# lotokey.net
KiCad netlist of a schematic drawn in EAGLE
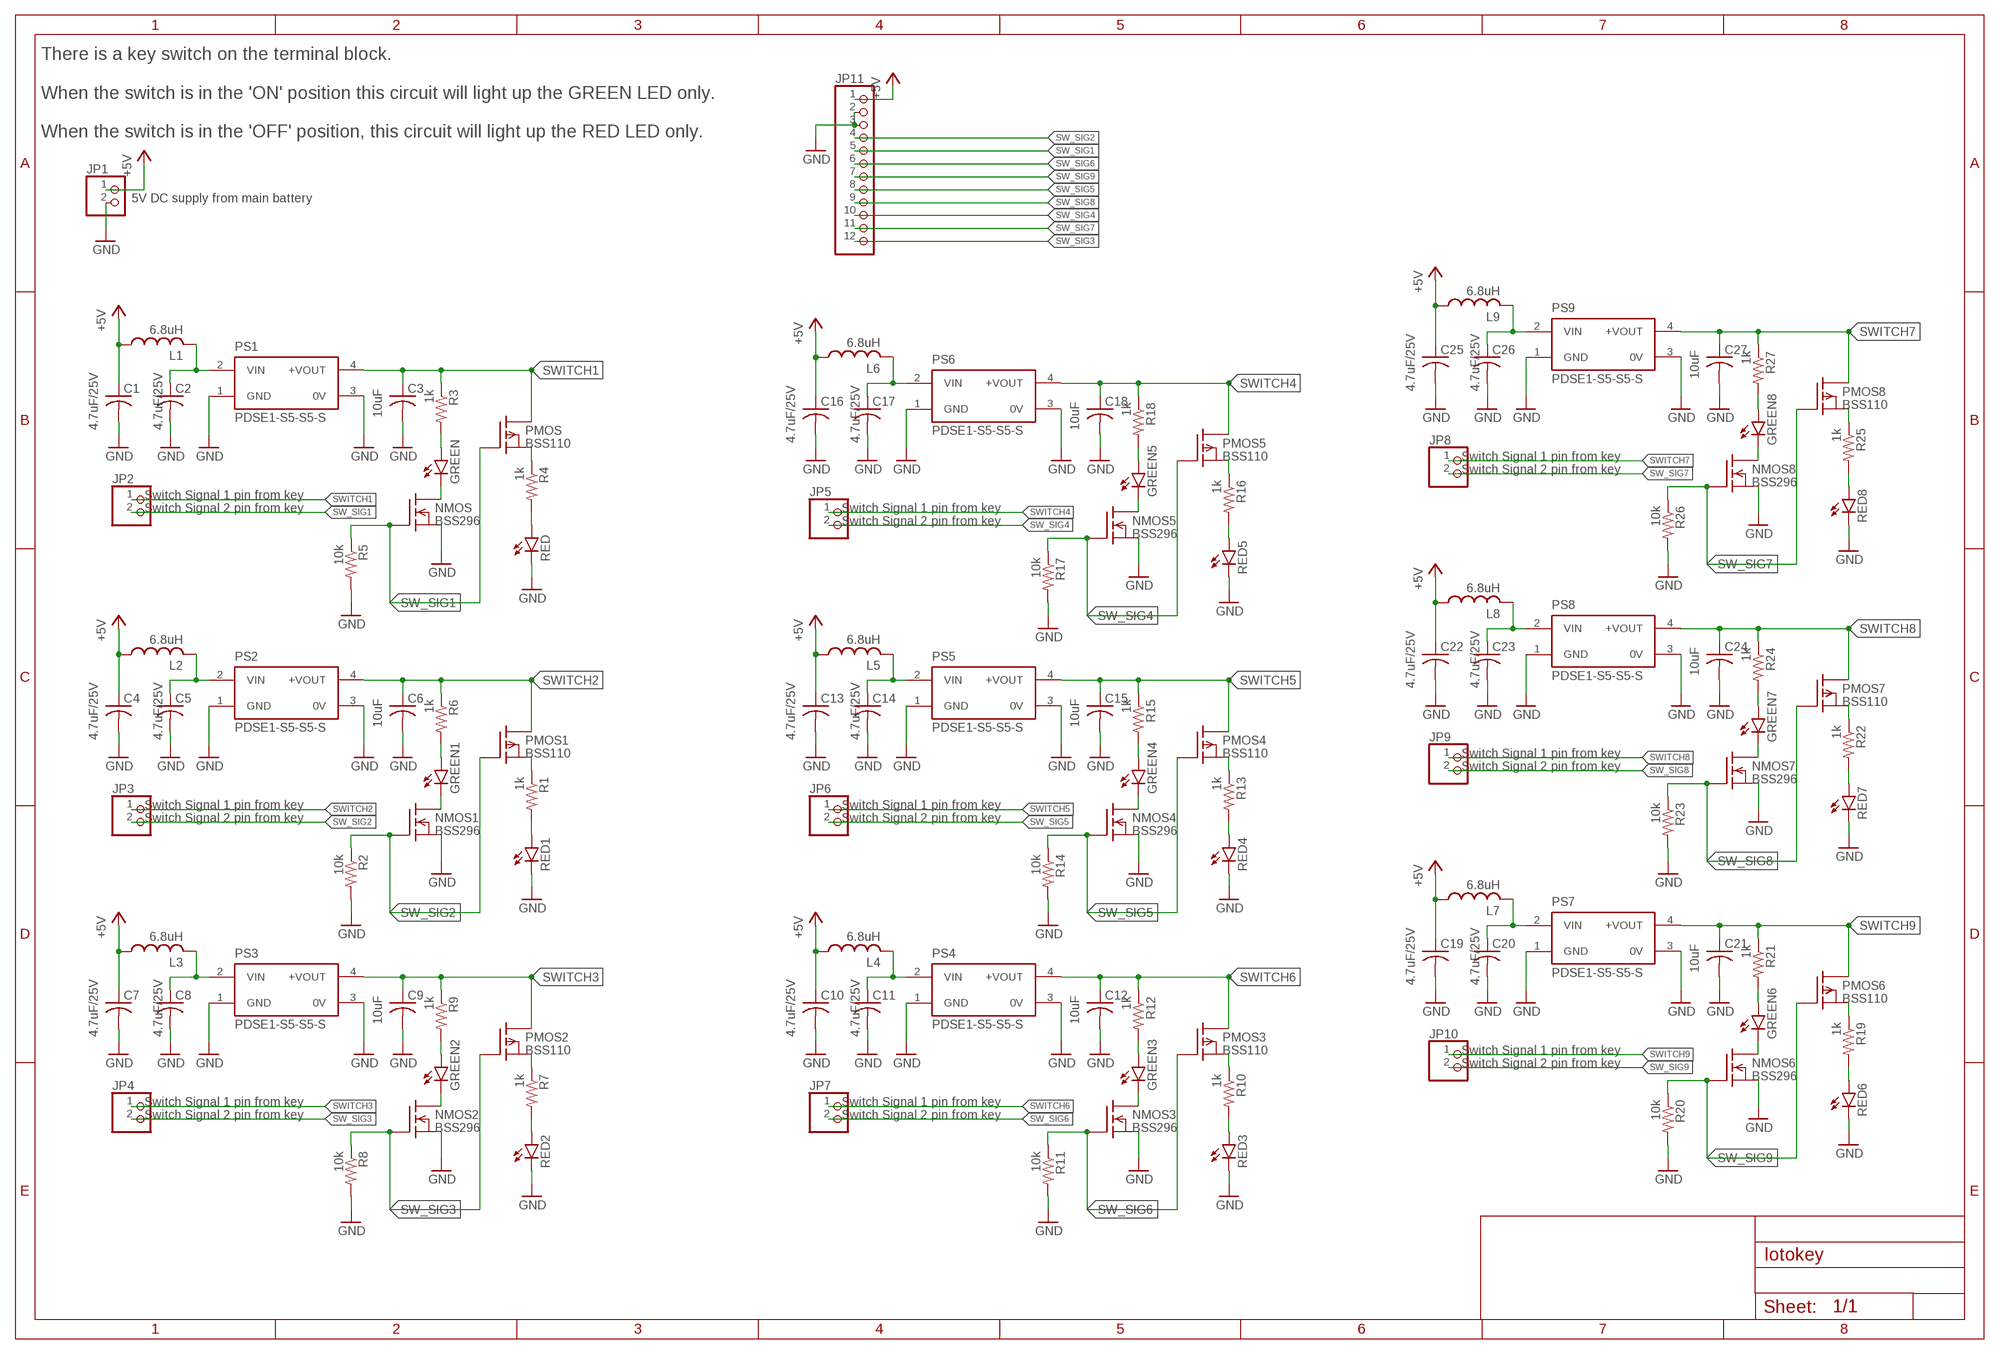
[diagram p0: schematic, sheet 1]

(export (version "E")
  (design (tool "Eeschema 10.0.6"))
  (components
    (comp (ref "C1")
      (value "4.7uF/25V")
      (footprint "eagle-import:C050-025X075")
      (fields (field (name "MFR") "TDK Corporation") (field (name "MPN") "FG28X5R1E475KRT06"))
      (libsource (lib "eagle-import") (part "C-US050-025X075"))
    )
    (comp (ref "C2")
      (value "4.7uF/25V")
      (footprint "eagle-import:C050-025X075")
      (fields (field (name "MFR") "TDK Corporation") (field (name "MPN") "FG28X5R1E475KRT06"))
      (libsource (lib "eagle-import") (part "C-US050-025X075"))
    )
    (comp (ref "C3")
      (value "10uF")
      (footprint "eagle-import:C050-025X075")
      (fields (field (name "MFR") "TDK Corporation") (field (name "MPN") "FG28X5R1E106MRT06"))
      (libsource (lib "eagle-import") (part "C-US050-025X075"))
    )
    (comp (ref "C4")
      (value "4.7uF/25V")
      (footprint "eagle-import:C050-025X075")
      (fields (field (name "MFR") "TDK Corporation") (field (name "MPN") "FG28X5R1E475KRT06"))
      (libsource (lib "eagle-import") (part "C-US050-025X075"))
    )
    (comp (ref "C5")
      (value "4.7uF/25V")
      (footprint "eagle-import:C050-025X075")
      (fields (field (name "MFR") "TDK Corporation") (field (name "MPN") "FG28X5R1E475KRT06"))
      (libsource (lib "eagle-import") (part "C-US050-025X075"))
    )
    (comp (ref "C6")
      (value "10uF")
      (footprint "eagle-import:C050-025X075")
      (fields (field (name "MFR") "TDK Corporation") (field (name "MPN") "FG28X5R1E106MRT06"))
      (libsource (lib "eagle-import") (part "C-US050-025X075"))
    )
    (comp (ref "C7")
      (value "4.7uF/25V")
      (footprint "eagle-import:C050-025X075")
      (fields (field (name "MFR") "TDK Corporation") (field (name "MPN") "FG28X5R1E475KRT06"))
      (libsource (lib "eagle-import") (part "C-US050-025X075"))
    )
    (comp (ref "C8")
      (value "4.7uF/25V")
      (footprint "eagle-import:C050-025X075")
      (fields (field (name "MFR") "TDK Corporation") (field (name "MPN") "FG28X5R1E475KRT06"))
      (libsource (lib "eagle-import") (part "C-US050-025X075"))
    )
    (comp (ref "C9")
      (value "10uF")
      (footprint "eagle-import:C050-025X075")
      (fields (field (name "MFR") "TDK Corporation") (field (name "MPN") "FG28X5R1E106MRT06"))
      (libsource (lib "eagle-import") (part "C-US050-025X075"))
    )
    (comp (ref "C10")
      (value "4.7uF/25V")
      (footprint "eagle-import:C050-025X075")
      (fields (field (name "MFR") "TDK Corporation") (field (name "MPN") "FG28X5R1E475KRT06"))
      (libsource (lib "eagle-import") (part "C-US050-025X075"))
    )
    (comp (ref "C11")
      (value "4.7uF/25V")
      (footprint "eagle-import:C050-025X075")
      (fields (field (name "MFR") "TDK Corporation") (field (name "MPN") "FG28X5R1E475KRT06"))
      (libsource (lib "eagle-import") (part "C-US050-025X075"))
    )
    (comp (ref "C12")
      (value "10uF")
      (footprint "eagle-import:C050-025X075")
      (fields (field (name "MFR") "TDK Corporation") (field (name "MPN") "FG28X5R1E106MRT06"))
      (libsource (lib "eagle-import") (part "C-US050-025X075"))
    )
    (comp (ref "C13")
      (value "4.7uF/25V")
      (footprint "eagle-import:C050-025X075")
      (fields (field (name "MFR") "TDK Corporation") (field (name "MPN") "FG28X5R1E475KRT06"))
      (libsource (lib "eagle-import") (part "C-US050-025X075"))
    )
    (comp (ref "C14")
      (value "4.7uF/25V")
      (footprint "eagle-import:C050-025X075")
      (fields (field (name "MFR") "TDK Corporation") (field (name "MPN") "FG28X5R1E475KRT06"))
      (libsource (lib "eagle-import") (part "C-US050-025X075"))
    )
    (comp (ref "C15")
      (value "10uF")
      (footprint "eagle-import:C050-025X075")
      (fields (field (name "MFR") "TDK Corporation") (field (name "MPN") "FG28X5R1E106MRT06"))
      (libsource (lib "eagle-import") (part "C-US050-025X075"))
    )
    (comp (ref "C16")
      (value "4.7uF/25V")
      (footprint "eagle-import:C050-025X075")
      (fields (field (name "MFR") "TDK Corporation") (field (name "MPN") "FG28X5R1E475KRT06"))
      (libsource (lib "eagle-import") (part "C-US050-025X075"))
    )
    (comp (ref "C17")
      (value "4.7uF/25V")
      (footprint "eagle-import:C050-025X075")
      (fields (field (name "MFR") "TDK Corporation") (field (name "MPN") "FG28X5R1E475KRT06"))
      (libsource (lib "eagle-import") (part "C-US050-025X075"))
    )
    (comp (ref "C18")
      (value "10uF")
      (footprint "eagle-import:C050-025X075")
      (fields (field (name "MFR") "TDK Corporation") (field (name "MPN") "FG28X5R1E106MRT06"))
      (libsource (lib "eagle-import") (part "C-US050-025X075"))
    )
    (comp (ref "C19")
      (value "4.7uF/25V")
      (footprint "eagle-import:C050-025X075")
      (fields (field (name "MFR") "TDK Corporation") (field (name "MPN") "FG28X5R1E475KRT06"))
      (libsource (lib "eagle-import") (part "C-US050-025X075"))
    )
    (comp (ref "C20")
      (value "4.7uF/25V")
      (footprint "eagle-import:C050-025X075")
      (fields (field (name "MFR") "TDK Corporation") (field (name "MPN") "FG28X5R1E475KRT06"))
      (libsource (lib "eagle-import") (part "C-US050-025X075"))
    )
    (comp (ref "C21")
      (value "10uF")
      (footprint "eagle-import:C050-025X075")
      (fields (field (name "MFR") "TDK Corporation") (field (name "MPN") "FG28X5R1E106MRT06"))
      (libsource (lib "eagle-import") (part "C-US050-025X075"))
    )
    (comp (ref "C22")
      (value "4.7uF/25V")
      (footprint "eagle-import:C050-025X075")
      (fields (field (name "MFR") "TDK Corporation") (field (name "MPN") "FG28X5R1E475KRT06"))
      (libsource (lib "eagle-import") (part "C-US050-025X075"))
    )
    (comp (ref "C23")
      (value "4.7uF/25V")
      (footprint "eagle-import:C050-025X075")
      (fields (field (name "MFR") "TDK Corporation") (field (name "MPN") "FG28X5R1E475KRT06"))
      (libsource (lib "eagle-import") (part "C-US050-025X075"))
    )
    (comp (ref "C24")
      (value "10uF")
      (footprint "eagle-import:C050-025X075")
      (fields (field (name "MFR") "TDK Corporation") (field (name "MPN") "FG28X5R1E106MRT06"))
      (libsource (lib "eagle-import") (part "C-US050-025X075"))
    )
    (comp (ref "C25")
      (value "4.7uF/25V")
      (footprint "eagle-import:C050-025X075")
      (fields (field (name "MFR") "TDK Corporation") (field (name "MPN") "FG28X5R1E475KRT06"))
      (libsource (lib "eagle-import") (part "C-US050-025X075"))
    )
    (comp (ref "C26")
      (value "4.7uF/25V")
      (footprint "eagle-import:C050-025X075")
      (fields (field (name "MFR") "TDK Corporation") (field (name "MPN") "FG28X5R1E475KRT06"))
      (libsource (lib "eagle-import") (part "C-US050-025X075"))
    )
    (comp (ref "C27")
      (value "10uF")
      (footprint "eagle-import:C050-025X075")
      (fields (field (name "MFR") "TDK Corporation") (field (name "MPN") "FG28X5R1E106MRT06"))
      (libsource (lib "eagle-import") (part "C-US050-025X075"))
    )
    (comp (ref "GREEN")
      (value "TLLR4400")
      (footprint "eagle-import:LED3MM")
      (fields
        (field (name "MF") "VISHAY SEMICONDUCTOR")
        (field (name "MFR") "Vishay Semiconductor Opto Division")
        (field (name "MPN") "TLHG5200")
      )
      (libsource (lib "eagle-import") (part "TLLR4400"))
    )
    (comp (ref "GREEN1")
      (value "TLLR4400")
      (footprint "eagle-import:LED3MM")
      (fields
        (field (name "MF") "VISHAY SEMICONDUCTOR")
        (field (name "MFR") "Vishay Semiconductor Opto Division")
        (field (name "MPN") "TLHG5200")
      )
      (libsource (lib "eagle-import") (part "TLLR4400"))
    )
    (comp (ref "GREEN2")
      (value "TLLR4400")
      (footprint "eagle-import:LED3MM")
      (fields
        (field (name "MF") "VISHAY SEMICONDUCTOR")
        (field (name "MFR") "Vishay Semiconductor Opto Division")
        (field (name "MPN") "TLHG5200")
      )
      (libsource (lib "eagle-import") (part "TLLR4400"))
    )
    (comp (ref "GREEN3")
      (value "TLLR4400")
      (footprint "eagle-import:LED3MM")
      (fields
        (field (name "MF") "VISHAY SEMICONDUCTOR")
        (field (name "MFR") "Vishay Semiconductor Opto Division")
        (field (name "MPN") "TLHG5200")
      )
      (libsource (lib "eagle-import") (part "TLLR4400"))
    )
    (comp (ref "GREEN4")
      (value "TLLR4400")
      (footprint "eagle-import:LED3MM")
      (fields
        (field (name "MF") "VISHAY SEMICONDUCTOR")
        (field (name "MFR") "Vishay Semiconductor Opto Division")
        (field (name "MPN") "TLHG5200")
      )
      (libsource (lib "eagle-import") (part "TLLR4400"))
    )
    (comp (ref "GREEN5")
      (value "TLLR4400")
      (footprint "eagle-import:LED3MM")
      (fields
        (field (name "MF") "VISHAY SEMICONDUCTOR")
        (field (name "MFR") "Vishay Semiconductor Opto Division")
        (field (name "MPN") "TLHG5200")
      )
      (libsource (lib "eagle-import") (part "TLLR4400"))
    )
    (comp (ref "GREEN6")
      (value "TLLR4400")
      (footprint "eagle-import:LED3MM")
      (fields
        (field (name "MF") "VISHAY SEMICONDUCTOR")
        (field (name "MFR") "Vishay Semiconductor Opto Division")
        (field (name "MPN") "TLHG5200")
      )
      (libsource (lib "eagle-import") (part "TLLR4400"))
    )
    (comp (ref "GREEN7")
      (value "TLLR4400")
      (footprint "eagle-import:LED3MM")
      (fields
        (field (name "MF") "VISHAY SEMICONDUCTOR")
        (field (name "MFR") "Vishay Semiconductor Opto Division")
        (field (name "MPN") "TLHG5200")
      )
      (libsource (lib "eagle-import") (part "TLLR4400"))
    )
    (comp (ref "GREEN8")
      (value "TLLR4400")
      (footprint "eagle-import:LED3MM")
      (fields
        (field (name "MF") "VISHAY SEMICONDUCTOR")
        (field (name "MFR") "Vishay Semiconductor Opto Division")
        (field (name "MPN") "TLHG5200")
      )
      (libsource (lib "eagle-import") (part "TLLR4400"))
    )
    (comp (ref "JP1")
      (value "PINHD-1X2")
      (footprint "eagle-import:1X02")
      (fields (field (name "MFR") "On Shore Technology Inc.") (field (name "MPN") "OSTVN02A150"))
      (libsource (lib "eagle-import") (part "PINHD-1X2"))
    )
    (comp (ref "JP2")
      (value "PINHD-1X2")
      (footprint "eagle-import:1X02")
      (fields (field (name "MFR") "On Shore Technology Inc.") (field (name "MPN") "OSTVN02A150"))
      (libsource (lib "eagle-import") (part "PINHD-1X2"))
    )
    (comp (ref "JP3")
      (value "PINHD-1X2")
      (footprint "eagle-import:1X02")
      (fields (field (name "MFR") "On Shore Technology Inc.") (field (name "MPN") "OSTVN02A150"))
      (libsource (lib "eagle-import") (part "PINHD-1X2"))
    )
    (comp (ref "JP4")
      (value "PINHD-1X2")
      (footprint "eagle-import:1X02")
      (fields (field (name "MFR") "On Shore Technology Inc.") (field (name "MPN") "OSTVN02A150"))
      (libsource (lib "eagle-import") (part "PINHD-1X2"))
    )
    (comp (ref "JP5")
      (value "PINHD-1X2")
      (footprint "eagle-import:1X02")
      (fields (field (name "MFR") "On Shore Technology Inc.") (field (name "MPN") "OSTVN02A150"))
      (libsource (lib "eagle-import") (part "PINHD-1X2"))
    )
    (comp (ref "JP6")
      (value "PINHD-1X2")
      (footprint "eagle-import:1X02")
      (fields (field (name "MFR") "On Shore Technology Inc.") (field (name "MPN") "OSTVN02A150"))
      (libsource (lib "eagle-import") (part "PINHD-1X2"))
    )
    (comp (ref "JP7")
      (value "PINHD-1X2")
      (footprint "eagle-import:1X02")
      (fields (field (name "MFR") "On Shore Technology Inc.") (field (name "MPN") "OSTVN02A150"))
      (libsource (lib "eagle-import") (part "PINHD-1X2"))
    )
    (comp (ref "JP8")
      (value "PINHD-1X2")
      (footprint "eagle-import:1X02")
      (fields (field (name "MFR") "On Shore Technology Inc.") (field (name "MPN") "OSTVN02A150"))
      (libsource (lib "eagle-import") (part "PINHD-1X2"))
    )
    (comp (ref "JP9")
      (value "PINHD-1X2")
      (footprint "eagle-import:1X02")
      (fields (field (name "MFR") "On Shore Technology Inc.") (field (name "MPN") "OSTVN02A150"))
      (libsource (lib "eagle-import") (part "PINHD-1X2"))
    )
    (comp (ref "JP10")
      (value "PINHD-1X2")
      (footprint "eagle-import:1X02")
      (fields (field (name "MFR") "On Shore Technology Inc.") (field (name "MPN") "OSTVN02A150"))
      (libsource (lib "eagle-import") (part "PINHD-1X2"))
    )
    (comp (ref "JP11")
      (value "PINHD-1X12")
      (footprint "eagle-import:1X12")
      (fields (field (name "MFR") "TE Connectivity AMP Connectors") (field (name "MPN") "1-640454-2"))
      (libsource (lib "eagle-import") (part "PINHD-1X12"))
    )
    (comp (ref "L1")
      (value "6.8uH")
      (footprint "eagle-import:0204_5")
      (fields (field (name "MFR") "EPCOS - TDK Electronics") (field (name "MPN") "B78108S1682K000"))
      (libsource (lib "eagle-import") (part "L-US0204/5"))
    )
    (comp (ref "L2")
      (value "6.8uH")
      (footprint "eagle-import:0204_5")
      (fields (field (name "MFR") "EPCOS - TDK Electronics") (field (name "MPN") "B78108S1682K000"))
      (libsource (lib "eagle-import") (part "L-US0204/5"))
    )
    (comp (ref "L3")
      (value "6.8uH")
      (footprint "eagle-import:0204_5")
      (fields (field (name "MFR") "EPCOS - TDK Electronics") (field (name "MPN") "B78108S1682K000"))
      (libsource (lib "eagle-import") (part "L-US0204/5"))
    )
    (comp (ref "L4")
      (value "6.8uH")
      (footprint "eagle-import:0204_5")
      (fields (field (name "MFR") "EPCOS - TDK Electronics") (field (name "MPN") "B78108S1682K000"))
      (libsource (lib "eagle-import") (part "L-US0204/5"))
    )
    (comp (ref "L5")
      (value "6.8uH")
      (footprint "eagle-import:0204_5")
      (fields (field (name "MFR") "EPCOS - TDK Electronics") (field (name "MPN") "B78108S1682K000"))
      (libsource (lib "eagle-import") (part "L-US0204/5"))
    )
    (comp (ref "L6")
      (value "6.8uH")
      (footprint "eagle-import:0204_5")
      (fields (field (name "MFR") "EPCOS - TDK Electronics") (field (name "MPN") "B78108S1682K000"))
      (libsource (lib "eagle-import") (part "L-US0204/5"))
    )
    (comp (ref "L7")
      (value "6.8uH")
      (footprint "eagle-import:0204_5")
      (fields (field (name "MFR") "EPCOS - TDK Electronics") (field (name "MPN") "B78108S1682K000"))
      (libsource (lib "eagle-import") (part "L-US0204/5"))
    )
    (comp (ref "L8")
      (value "6.8uH")
      (footprint "eagle-import:0204_5")
      (fields (field (name "MFR") "EPCOS - TDK Electronics") (field (name "MPN") "B78108S1682K000"))
      (libsource (lib "eagle-import") (part "L-US0204/5"))
    )
    (comp (ref "L9")
      (value "6.8uH")
      (footprint "eagle-import:0204_5")
      (fields (field (name "MFR") "EPCOS - TDK Electronics") (field (name "MPN") "B78108S1682K000"))
      (libsource (lib "eagle-import") (part "L-US0204/5"))
    )
    (comp (ref "NMOS")
      (value "BSS296")
      (footprint "eagle-import:TO92")
      (fields (field (name "MFR") "Microchip Technology") (field (name "MPN") "2N7000-G"))
      (libsource (lib "eagle-import") (part "BSS296"))
    )
    (comp (ref "NMOS1")
      (value "BSS296")
      (footprint "eagle-import:TO92")
      (fields (field (name "MFR") "Microchip Technology") (field (name "MPN") "2N7000-G"))
      (libsource (lib "eagle-import") (part "BSS296"))
    )
    (comp (ref "NMOS2")
      (value "BSS296")
      (footprint "eagle-import:TO92")
      (fields (field (name "MFR") "Microchip Technology") (field (name "MPN") "2N7000-G"))
      (libsource (lib "eagle-import") (part "BSS296"))
    )
    (comp (ref "NMOS3")
      (value "BSS296")
      (footprint "eagle-import:TO92")
      (fields (field (name "MFR") "Microchip Technology") (field (name "MPN") "2N7000-G"))
      (libsource (lib "eagle-import") (part "BSS296"))
    )
    (comp (ref "NMOS4")
      (value "BSS296")
      (footprint "eagle-import:TO92")
      (fields (field (name "MFR") "Microchip Technology") (field (name "MPN") "2N7000-G"))
      (libsource (lib "eagle-import") (part "BSS296"))
    )
    (comp (ref "NMOS5")
      (value "BSS296")
      (footprint "eagle-import:TO92")
      (fields (field (name "MFR") "Microchip Technology") (field (name "MPN") "2N7000-G"))
      (libsource (lib "eagle-import") (part "BSS296"))
    )
    (comp (ref "NMOS6")
      (value "BSS296")
      (footprint "eagle-import:TO92")
      (fields (field (name "MFR") "Microchip Technology") (field (name "MPN") "2N7000-G"))
      (libsource (lib "eagle-import") (part "BSS296"))
    )
    (comp (ref "NMOS7")
      (value "BSS296")
      (footprint "eagle-import:TO92")
      (fields (field (name "MFR") "Microchip Technology") (field (name "MPN") "2N7000-G"))
      (libsource (lib "eagle-import") (part "BSS296"))
    )
    (comp (ref "NMOS8")
      (value "BSS296")
      (footprint "eagle-import:TO92")
      (fields (field (name "MFR") "Microchip Technology") (field (name "MPN") "2N7000-G"))
      (libsource (lib "eagle-import") (part "BSS296"))
    )
    (comp (ref "PMOS")
      (value "BSS110")
      (footprint "eagle-import:TO92")
      (fields (field (name "MFR") "Microchip Technology") (field (name "MPN") "TP2104N3-G"))
      (libsource (lib "eagle-import") (part "BSS110"))
    )
    (comp (ref "PMOS1")
      (value "BSS110")
      (footprint "eagle-import:TO92")
      (fields (field (name "MFR") "Microchip Technology") (field (name "MPN") "TP2104N3-G"))
      (libsource (lib "eagle-import") (part "BSS110"))
    )
    (comp (ref "PMOS2")
      (value "BSS110")
      (footprint "eagle-import:TO92")
      (fields (field (name "MFR") "Microchip Technology") (field (name "MPN") "TP2104N3-G"))
      (libsource (lib "eagle-import") (part "BSS110"))
    )
    (comp (ref "PMOS3")
      (value "BSS110")
      (footprint "eagle-import:TO92")
      (fields (field (name "MFR") "Microchip Technology") (field (name "MPN") "TP2104N3-G"))
      (libsource (lib "eagle-import") (part "BSS110"))
    )
    (comp (ref "PMOS4")
      (value "BSS110")
      (footprint "eagle-import:TO92")
      (fields (field (name "MFR") "Microchip Technology") (field (name "MPN") "TP2104N3-G"))
      (libsource (lib "eagle-import") (part "BSS110"))
    )
    (comp (ref "PMOS5")
      (value "BSS110")
      (footprint "eagle-import:TO92")
      (fields (field (name "MFR") "Microchip Technology") (field (name "MPN") "TP2104N3-G"))
      (libsource (lib "eagle-import") (part "BSS110"))
    )
    (comp (ref "PMOS6")
      (value "BSS110")
      (footprint "eagle-import:TO92")
      (fields (field (name "MFR") "Microchip Technology") (field (name "MPN") "TP2104N3-G"))
      (libsource (lib "eagle-import") (part "BSS110"))
    )
    (comp (ref "PMOS7")
      (value "BSS110")
      (footprint "eagle-import:TO92")
      (fields (field (name "MFR") "Microchip Technology") (field (name "MPN") "TP2104N3-G"))
      (libsource (lib "eagle-import") (part "BSS110"))
    )
    (comp (ref "PMOS8")
      (value "BSS110")
      (footprint "eagle-import:TO92")
      (fields (field (name "MFR") "Microchip Technology") (field (name "MPN") "TP2104N3-G"))
      (libsource (lib "eagle-import") (part "BSS110"))
    )
    (comp (ref "PS1")
      (value "PDSE1-S5-S5-S")
      (footprint "eagle-import:CONV_PDSE1-S5-S5-S")
      (fields (field (name "DIGI-KEY_PART_NUMBER") "102-6291-ND") (field (name "MF") "CUI Inc."))
      (libsource (lib "eagle-import") (part "PDSE1-S5-S5-S"))
    )
    (comp (ref "PS2")
      (value "PDSE1-S5-S5-S")
      (footprint "eagle-import:CONV_PDSE1-S5-S5-S")
      (fields (field (name "DIGI-KEY_PART_NUMBER") "102-6291-ND") (field (name "MF") "CUI Inc."))
      (libsource (lib "eagle-import") (part "PDSE1-S5-S5-S"))
    )
    (comp (ref "PS3")
      (value "PDSE1-S5-S5-S")
      (footprint "eagle-import:CONV_PDSE1-S5-S5-S")
      (fields (field (name "DIGI-KEY_PART_NUMBER") "102-6291-ND") (field (name "MF") "CUI Inc."))
      (libsource (lib "eagle-import") (part "PDSE1-S5-S5-S"))
    )
    (comp (ref "PS4")
      (value "PDSE1-S5-S5-S")
      (footprint "eagle-import:CONV_PDSE1-S5-S5-S")
      (fields (field (name "DIGI-KEY_PART_NUMBER") "102-6291-ND") (field (name "MF") "CUI Inc."))
      (libsource (lib "eagle-import") (part "PDSE1-S5-S5-S"))
    )
    (comp (ref "PS5")
      (value "PDSE1-S5-S5-S")
      (footprint "eagle-import:CONV_PDSE1-S5-S5-S")
      (fields (field (name "DIGI-KEY_PART_NUMBER") "102-6291-ND") (field (name "MF") "CUI Inc."))
      (libsource (lib "eagle-import") (part "PDSE1-S5-S5-S"))
    )
    (comp (ref "PS6")
      (value "PDSE1-S5-S5-S")
      (footprint "eagle-import:CONV_PDSE1-S5-S5-S")
      (fields (field (name "DIGI-KEY_PART_NUMBER") "102-6291-ND") (field (name "MF") "CUI Inc."))
      (libsource (lib "eagle-import") (part "PDSE1-S5-S5-S"))
    )
    (comp (ref "PS7")
      (value "PDSE1-S5-S5-S")
      (footprint "eagle-import:CONV_PDSE1-S5-S5-S")
      (fields (field (name "DIGI-KEY_PART_NUMBER") "102-6291-ND") (field (name "MF") "CUI Inc."))
      (libsource (lib "eagle-import") (part "PDSE1-S5-S5-S"))
    )
    (comp (ref "PS8")
      (value "PDSE1-S5-S5-S")
      (footprint "eagle-import:CONV_PDSE1-S5-S5-S")
      (fields (field (name "DIGI-KEY_PART_NUMBER") "102-6291-ND") (field (name "MF") "CUI Inc."))
      (libsource (lib "eagle-import") (part "PDSE1-S5-S5-S"))
    )
    (comp (ref "PS9")
      (value "PDSE1-S5-S5-S")
      (footprint "eagle-import:CONV_PDSE1-S5-S5-S")
      (fields (field (name "DIGI-KEY_PART_NUMBER") "102-6291-ND") (field (name "MF") "CUI Inc."))
      (libsource (lib "eagle-import") (part "PDSE1-S5-S5-S"))
    )
    (comp (ref "R1")
      (value "1k")
      (footprint "eagle-import:0204_7")
      (fields
        (field (name "MFR") "Vishay Beyschlag/Draloric/BC Components")
        (field (name "MPN") "CCF551K00FKE36")
      )
      (libsource (lib "eagle-import") (part "R-US_0204/7"))
    )
    (comp (ref "R2")
      (value "10k")
      (footprint "eagle-import:0204_7")
      (fields
        (field (name "MFR") "Vishay Beyschlag/Draloric/BC Components")
        (field (name "MPN") "CCF5510K0FKE36")
      )
      (libsource (lib "eagle-import") (part "R-US_0204/7"))
    )
    (comp (ref "R3")
      (value "1k")
      (footprint "eagle-import:0204_7")
      (fields
        (field (name "MFR") "Vishay Beyschlag/Draloric/BC Components")
        (field (name "MPN") "CCF551K00FKE36")
      )
      (libsource (lib "eagle-import") (part "R-US_0204/7"))
    )
    (comp (ref "R4")
      (value "1k")
      (footprint "eagle-import:0204_7")
      (fields
        (field (name "MFR") "Vishay Beyschlag/Draloric/BC Components")
        (field (name "MPN") "CCF551K00FKE36")
      )
      (libsource (lib "eagle-import") (part "R-US_0204/7"))
    )
    (comp (ref "R5")
      (value "10k")
      (footprint "eagle-import:0204_7")
      (fields
        (field (name "MFR") "Vishay Beyschlag/Draloric/BC Components")
        (field (name "MPN") "CCF5510K0FKE36")
      )
      (libsource (lib "eagle-import") (part "R-US_0204/7"))
    )
    (comp (ref "R6")
      (value "1k")
      (footprint "eagle-import:0204_7")
      (fields
        (field (name "MFR") "Vishay Beyschlag/Draloric/BC Components")
        (field (name "MPN") "CCF551K00FKE36")
      )
      (libsource (lib "eagle-import") (part "R-US_0204/7"))
    )
    (comp (ref "R7")
      (value "1k")
      (footprint "eagle-import:0204_7")
      (fields
        (field (name "MFR") "Vishay Beyschlag/Draloric/BC Components")
        (field (name "MPN") "CCF551K00FKE36")
      )
      (libsource (lib "eagle-import") (part "R-US_0204/7"))
    )
    (comp (ref "R8")
      (value "10k")
      (footprint "eagle-import:0204_7")
      (fields
        (field (name "MFR") "Vishay Beyschlag/Draloric/BC Components")
        (field (name "MPN") "CCF5510K0FKE36")
      )
      (libsource (lib "eagle-import") (part "R-US_0204/7"))
    )
    (comp (ref "R9")
      (value "1k")
      (footprint "eagle-import:0204_7")
      (fields
        (field (name "MFR") "Vishay Beyschlag/Draloric/BC Components")
        (field (name "MPN") "CCF551K00FKE36")
      )
      (libsource (lib "eagle-import") (part "R-US_0204/7"))
    )
    (comp (ref "R10")
      (value "1k")
      (footprint "eagle-import:0204_7")
      (fields
        (field (name "MFR") "Vishay Beyschlag/Draloric/BC Components")
        (field (name "MPN") "CCF551K00FKE36")
      )
      (libsource (lib "eagle-import") (part "R-US_0204/7"))
    )
    (comp (ref "R11")
      (value "10k")
      (footprint "eagle-import:0204_7")
      (fields
        (field (name "MFR") "Vishay Beyschlag/Draloric/BC Components")
        (field (name "MPN") "CCF5510K0FKE36")
      )
      (libsource (lib "eagle-import") (part "R-US_0204/7"))
    )
    (comp (ref "R12")
      (value "1k")
      (footprint "eagle-import:0204_7")
      (fields
        (field (name "MFR") "Vishay Beyschlag/Draloric/BC Components")
        (field (name "MPN") "CCF551K00FKE36")
      )
      (libsource (lib "eagle-import") (part "R-US_0204/7"))
    )
    (comp (ref "R13")
      (value "1k")
      (footprint "eagle-import:0204_7")
      (fields
        (field (name "MFR") "Vishay Beyschlag/Draloric/BC Components")
        (field (name "MPN") "CCF551K00FKE36")
      )
      (libsource (lib "eagle-import") (part "R-US_0204/7"))
    )
    (comp (ref "R14")
      (value "10k")
      (footprint "eagle-import:0204_7")
      (fields
        (field (name "MFR") "Vishay Beyschlag/Draloric/BC Components")
        (field (name "MPN") "CCF5510K0FKE36")
      )
      (libsource (lib "eagle-import") (part "R-US_0204/7"))
    )
    (comp (ref "R15")
      (value "1k")
      (footprint "eagle-import:0204_7")
      (fields
        (field (name "MFR") "Vishay Beyschlag/Draloric/BC Components")
        (field (name "MPN") "CCF551K00FKE36")
      )
      (libsource (lib "eagle-import") (part "R-US_0204/7"))
    )
    (comp (ref "R16")
      (value "1k")
      (footprint "eagle-import:0204_7")
      (fields
        (field (name "MFR") "Vishay Beyschlag/Draloric/BC Components")
        (field (name "MPN") "CCF551K00FKE36")
      )
      (libsource (lib "eagle-import") (part "R-US_0204/7"))
    )
    (comp (ref "R17")
      (value "10k")
      (footprint "eagle-import:0204_7")
      (fields
        (field (name "MFR") "Vishay Beyschlag/Draloric/BC Components")
        (field (name "MPN") "CCF5510K0FKE36")
      )
      (libsource (lib "eagle-import") (part "R-US_0204/7"))
    )
    (comp (ref "R18")
      (value "1k")
      (footprint "eagle-import:0204_7")
      (fields
        (field (name "MFR") "Vishay Beyschlag/Draloric/BC Components")
        (field (name "MPN") "CCF551K00FKE36")
      )
      (libsource (lib "eagle-import") (part "R-US_0204/7"))
    )
    (comp (ref "R19")
      (value "1k")
      (footprint "eagle-import:0204_7")
      (fields
        (field (name "MFR") "Vishay Beyschlag/Draloric/BC Components")
        (field (name "MPN") "CCF551K00FKE36")
      )
      (libsource (lib "eagle-import") (part "R-US_0204/7"))
    )
    (comp (ref "R20")
      (value "10k")
      (footprint "eagle-import:0204_7")
      (fields
        (field (name "MFR") "Vishay Beyschlag/Draloric/BC Components")
        (field (name "MPN") "CCF5510K0FKE36")
      )
      (libsource (lib "eagle-import") (part "R-US_0204/7"))
    )
    (comp (ref "R21")
      (value "1k")
      (footprint "eagle-import:0204_7")
      (fields
        (field (name "MFR") "Vishay Beyschlag/Draloric/BC Components")
        (field (name "MPN") "CCF551K00FKE36")
      )
      (libsource (lib "eagle-import") (part "R-US_0204/7"))
    )
    (comp (ref "R22")
      (value "1k")
      (footprint "eagle-import:0204_7")
      (fields
        (field (name "MFR") "Vishay Beyschlag/Draloric/BC Components")
        (field (name "MPN") "CCF551K00FKE36")
      )
      (libsource (lib "eagle-import") (part "R-US_0204/7"))
    )
    (comp (ref "R23")
      (value "10k")
      (footprint "eagle-import:0204_7")
      (fields
        (field (name "MFR") "Vishay Beyschlag/Draloric/BC Components")
        (field (name "MPN") "CCF5510K0FKE36")
      )
      (libsource (lib "eagle-import") (part "R-US_0204/7"))
    )
    (comp (ref "R24")
      (value "1k")
      (footprint "eagle-import:0204_7")
      (fields
        (field (name "MFR") "Vishay Beyschlag/Draloric/BC Components")
        (field (name "MPN") "CCF551K00FKE36")
      )
      (libsource (lib "eagle-import") (part "R-US_0204/7"))
    )
    (comp (ref "R25")
      (value "1k")
      (footprint "eagle-import:0204_7")
      (fields
        (field (name "MFR") "Vishay Beyschlag/Draloric/BC Components")
        (field (name "MPN") "CCF551K00FKE36")
      )
      (libsource (lib "eagle-import") (part "R-US_0204/7"))
    )
    (comp (ref "R26")
      (value "10k")
      (footprint "eagle-import:0204_7")
      (fields
        (field (name "MFR") "Vishay Beyschlag/Draloric/BC Components")
        (field (name "MPN") "CCF5510K0FKE36")
      )
      (libsource (lib "eagle-import") (part "R-US_0204/7"))
    )
    (comp (ref "R27")
      (value "1k")
      (footprint "eagle-import:0204_7")
      (fields
        (field (name "MFR") "Vishay Beyschlag/Draloric/BC Components")
        (field (name "MPN") "CCF551K00FKE36")
      )
      (libsource (lib "eagle-import") (part "R-US_0204/7"))
    )
    (comp (ref "RED")
      (value "TLLR4400")
      (footprint "eagle-import:LED3MM")
      (fields
        (field (name "MF") "VISHAY SEMICONDUCTOR")
        (field (name "MFR") "Vishay Semiconductor Opto Division")
        (field (name "MPN") "TLUR6400")
      )
      (libsource (lib "eagle-import") (part "TLLR4400"))
    )
    (comp (ref "RED1")
      (value "TLLR4400")
      (footprint "eagle-import:LED3MM")
      (fields
        (field (name "MF") "VISHAY SEMICONDUCTOR")
        (field (name "MFR") "Vishay Semiconductor Opto Division")
        (field (name "MPN") "TLUR6400")
      )
      (libsource (lib "eagle-import") (part "TLLR4400"))
    )
    (comp (ref "RED2")
      (value "TLLR4400")
      (footprint "eagle-import:LED3MM")
      (fields
        (field (name "MF") "VISHAY SEMICONDUCTOR")
        (field (name "MFR") "Vishay Semiconductor Opto Division")
        (field (name "MPN") "TLUR6400")
      )
      (libsource (lib "eagle-import") (part "TLLR4400"))
    )
    (comp (ref "RED3")
      (value "TLLR4400")
      (footprint "eagle-import:LED3MM")
      (fields
        (field (name "MF") "VISHAY SEMICONDUCTOR")
        (field (name "MFR") "Vishay Semiconductor Opto Division")
        (field (name "MPN") "TLUR6400")
      )
      (libsource (lib "eagle-import") (part "TLLR4400"))
    )
    (comp (ref "RED4")
      (value "TLLR4400")
      (footprint "eagle-import:LED3MM")
      (fields
        (field (name "MF") "VISHAY SEMICONDUCTOR")
        (field (name "MFR") "Vishay Semiconductor Opto Division")
        (field (name "MPN") "TLUR6400")
      )
      (libsource (lib "eagle-import") (part "TLLR4400"))
    )
    (comp (ref "RED5")
      (value "TLLR4400")
      (footprint "eagle-import:LED3MM")
      (fields
        (field (name "MF") "VISHAY SEMICONDUCTOR")
        (field (name "MFR") "Vishay Semiconductor Opto Division")
        (field (name "MPN") "TLUR6400")
      )
      (libsource (lib "eagle-import") (part "TLLR4400"))
    )
    (comp (ref "RED6")
      (value "TLLR4400")
      (footprint "eagle-import:LED3MM")
      (fields
        (field (name "MF") "VISHAY SEMICONDUCTOR")
        (field (name "MFR") "Vishay Semiconductor Opto Division")
        (field (name "MPN") "TLUR6400")
      )
      (libsource (lib "eagle-import") (part "TLLR4400"))
    )
    (comp (ref "RED7")
      (value "TLLR4400")
      (footprint "eagle-import:LED3MM")
      (fields
        (field (name "MF") "VISHAY SEMICONDUCTOR")
        (field (name "MFR") "Vishay Semiconductor Opto Division")
        (field (name "MPN") "TLUR6400")
      )
      (libsource (lib "eagle-import") (part "TLLR4400"))
    )
    (comp (ref "RED8")
      (value "TLLR4400")
      (footprint "eagle-import:LED3MM")
      (fields
        (field (name "MF") "VISHAY SEMICONDUCTOR")
        (field (name "MFR") "Vishay Semiconductor Opto Division")
        (field (name "MPN") "TLUR6400")
      )
      (libsource (lib "eagle-import") (part "TLLR4400"))
    )
  )
  (nets
    (net (code "1") (name "+5V") (class "Default")
      (node (ref "C1") (pin "1") (pinfunction "1_1") (pintype "passive"))
      (node (ref "C10") (pin "1") (pinfunction "1_1") (pintype "passive"))
      (node (ref "C13") (pin "1") (pinfunction "1_1") (pintype "passive"))
      (node (ref "C16") (pin "1") (pinfunction "1_1") (pintype "passive"))
      (node (ref "C19") (pin "1") (pinfunction "1_1") (pintype "passive"))
      (node (ref "C22") (pin "1") (pinfunction "1_1") (pintype "passive"))
      (node (ref "C25") (pin "1") (pinfunction "1_1") (pintype "passive"))
      (node (ref "C4") (pin "1") (pinfunction "1_1") (pintype "passive"))
      (node (ref "C7") (pin "1") (pinfunction "1_1") (pintype "passive"))
      (node (ref "JP1") (pin "1") (pinfunction "1_1") (pintype "passive"))
      (node (ref "JP11") (pin "1") (pinfunction "1_1") (pintype "passive"))
      (node (ref "L1") (pin "1") (pinfunction "1_1") (pintype "passive"))
      (node (ref "L2") (pin "1") (pinfunction "1_1") (pintype "passive"))
      (node (ref "L3") (pin "1") (pinfunction "1_1") (pintype "passive"))
      (node (ref "L4") (pin "1") (pinfunction "1_1") (pintype "passive"))
      (node (ref "L5") (pin "1") (pinfunction "1_1") (pintype "passive"))
      (node (ref "L6") (pin "1") (pinfunction "1_1") (pintype "passive"))
      (node (ref "L7") (pin "1") (pinfunction "1_1") (pintype "passive"))
      (node (ref "L8") (pin "1") (pinfunction "1_1") (pintype "passive"))
      (node (ref "L9") (pin "1") (pinfunction "1_1") (pintype "passive"))
    )
    (net (code "2") (name "GND") (class "Default")
      (node (ref "C1") (pin "2") (pinfunction "2_2") (pintype "passive"))
      (node (ref "C10") (pin "2") (pinfunction "2_2") (pintype "passive"))
      (node (ref "C11") (pin "2") (pinfunction "2_2") (pintype "passive"))
      (node (ref "C12") (pin "2") (pinfunction "2_2") (pintype "passive"))
      (node (ref "C13") (pin "2") (pinfunction "2_2") (pintype "passive"))
      (node (ref "C14") (pin "2") (pinfunction "2_2") (pintype "passive"))
      (node (ref "C15") (pin "2") (pinfunction "2_2") (pintype "passive"))
      (node (ref "C16") (pin "2") (pinfunction "2_2") (pintype "passive"))
      (node (ref "C17") (pin "2") (pinfunction "2_2") (pintype "passive"))
      (node (ref "C18") (pin "2") (pinfunction "2_2") (pintype "passive"))
      (node (ref "C19") (pin "2") (pinfunction "2_2") (pintype "passive"))
      (node (ref "C2") (pin "2") (pinfunction "2_2") (pintype "passive"))
      (node (ref "C20") (pin "2") (pinfunction "2_2") (pintype "passive"))
      (node (ref "C21") (pin "2") (pinfunction "2_2") (pintype "passive"))
      (node (ref "C22") (pin "2") (pinfunction "2_2") (pintype "passive"))
      (node (ref "C23") (pin "2") (pinfunction "2_2") (pintype "passive"))
      (node (ref "C24") (pin "2") (pinfunction "2_2") (pintype "passive"))
      (node (ref "C25") (pin "2") (pinfunction "2_2") (pintype "passive"))
      (node (ref "C26") (pin "2") (pinfunction "2_2") (pintype "passive"))
      (node (ref "C27") (pin "2") (pinfunction "2_2") (pintype "passive"))
      (node (ref "C3") (pin "2") (pinfunction "2_2") (pintype "passive"))
      (node (ref "C4") (pin "2") (pinfunction "2_2") (pintype "passive"))
      (node (ref "C5") (pin "2") (pinfunction "2_2") (pintype "passive"))
      (node (ref "C6") (pin "2") (pinfunction "2_2") (pintype "passive"))
      (node (ref "C7") (pin "2") (pinfunction "2_2") (pintype "passive"))
      (node (ref "C8") (pin "2") (pinfunction "2_2") (pintype "passive"))
      (node (ref "C9") (pin "2") (pinfunction "2_2") (pintype "passive"))
      (node (ref "JP1") (pin "2") (pinfunction "2_2") (pintype "passive"))
      (node (ref "JP11") (pin "2") (pinfunction "2_2") (pintype "passive"))
      (node (ref "JP11") (pin "3") (pinfunction "3_3") (pintype "passive"))
      (node (ref "NMOS") (pin "3") (pinfunction "S_3") (pintype "passive"))
      (node (ref "NMOS1") (pin "3") (pinfunction "S_3") (pintype "passive"))
      (node (ref "NMOS2") (pin "3") (pinfunction "S_3") (pintype "passive"))
      (node (ref "NMOS3") (pin "3") (pinfunction "S_3") (pintype "passive"))
      (node (ref "NMOS4") (pin "3") (pinfunction "S_3") (pintype "passive"))
      (node (ref "NMOS5") (pin "3") (pinfunction "S_3") (pintype "passive"))
      (node (ref "NMOS6") (pin "3") (pinfunction "S_3") (pintype "passive"))
      (node (ref "NMOS7") (pin "3") (pinfunction "S_3") (pintype "passive"))
      (node (ref "NMOS8") (pin "3") (pinfunction "S_3") (pintype "passive"))
      (node (ref "PS1") (pin "1") (pinfunction "GND_1") (pintype "power_in"))
      (node (ref "PS1") (pin "3") (pinfunction "0V_3") (pintype "power_in"))
      (node (ref "PS2") (pin "1") (pinfunction "GND_1") (pintype "power_in"))
      (node (ref "PS2") (pin "3") (pinfunction "0V_3") (pintype "power_in"))
      (node (ref "PS3") (pin "1") (pinfunction "GND_1") (pintype "power_in"))
      (node (ref "PS3") (pin "3") (pinfunction "0V_3") (pintype "power_in"))
      (node (ref "PS4") (pin "1") (pinfunction "GND_1") (pintype "power_in"))
      (node (ref "PS4") (pin "3") (pinfunction "0V_3") (pintype "power_in"))
      (node (ref "PS5") (pin "1") (pinfunction "GND_1") (pintype "power_in"))
      (node (ref "PS5") (pin "3") (pinfunction "0V_3") (pintype "power_in"))
      (node (ref "PS6") (pin "1") (pinfunction "GND_1") (pintype "power_in"))
      (node (ref "PS6") (pin "3") (pinfunction "0V_3") (pintype "power_in"))
      (node (ref "PS7") (pin "1") (pinfunction "GND_1") (pintype "power_in"))
      (node (ref "PS7") (pin "3") (pinfunction "0V_3") (pintype "power_in"))
      (node (ref "PS8") (pin "1") (pinfunction "GND_1") (pintype "power_in"))
      (node (ref "PS8") (pin "3") (pinfunction "0V_3") (pintype "power_in"))
      (node (ref "PS9") (pin "1") (pinfunction "GND_1") (pintype "power_in"))
      (node (ref "PS9") (pin "3") (pinfunction "0V_3") (pintype "power_in"))
      (node (ref "R11") (pin "2") (pinfunction "2_2") (pintype "passive"))
      (node (ref "R14") (pin "2") (pinfunction "2_2") (pintype "passive"))
      (node (ref "R17") (pin "2") (pinfunction "2_2") (pintype "passive"))
      (node (ref "R2") (pin "2") (pinfunction "2_2") (pintype "passive"))
      (node (ref "R20") (pin "2") (pinfunction "2_2") (pintype "passive"))
      (node (ref "R23") (pin "2") (pinfunction "2_2") (pintype "passive"))
      (node (ref "R26") (pin "2") (pinfunction "2_2") (pintype "passive"))
      (node (ref "R5") (pin "2") (pinfunction "2_2") (pintype "passive"))
      (node (ref "R8") (pin "2") (pinfunction "2_2") (pintype "passive"))
      (node (ref "RED") (pin "K") (pinfunction "C_K") (pintype "passive"))
      (node (ref "RED1") (pin "K") (pinfunction "C_K") (pintype "passive"))
      (node (ref "RED2") (pin "K") (pinfunction "C_K") (pintype "passive"))
      (node (ref "RED3") (pin "K") (pinfunction "C_K") (pintype "passive"))
      (node (ref "RED4") (pin "K") (pinfunction "C_K") (pintype "passive"))
      (node (ref "RED5") (pin "K") (pinfunction "C_K") (pintype "passive"))
      (node (ref "RED6") (pin "K") (pinfunction "C_K") (pintype "passive"))
      (node (ref "RED7") (pin "K") (pinfunction "C_K") (pintype "passive"))
      (node (ref "RED8") (pin "K") (pinfunction "C_K") (pintype "passive"))
    )
    (net (code "3") (name "Net-(GREEN-C)") (class "Default")
      (node (ref "GREEN") (pin "K") (pinfunction "C_K") (pintype "passive"))
      (node (ref "NMOS") (pin "2") (pinfunction "D_2") (pintype "passive"))
    )
    (net (code "4") (name "Net-(GREEN-PadA)") (class "Default")
      (node (ref "GREEN") (pin "A") (pinfunction "A_A") (pintype "passive"))
      (node (ref "R3") (pin "2") (pinfunction "2_2") (pintype "passive"))
    )
    (net (code "5") (name "Net-(GREEN1-C)") (class "Default")
      (node (ref "GREEN1") (pin "K") (pinfunction "C_K") (pintype "passive"))
      (node (ref "NMOS1") (pin "2") (pinfunction "D_2") (pintype "passive"))
    )
    (net (code "6") (name "Net-(GREEN1-PadA)") (class "Default")
      (node (ref "GREEN1") (pin "A") (pinfunction "A_A") (pintype "passive"))
      (node (ref "R6") (pin "2") (pinfunction "2_2") (pintype "passive"))
    )
    (net (code "7") (name "Net-(GREEN2-C)") (class "Default")
      (node (ref "GREEN2") (pin "K") (pinfunction "C_K") (pintype "passive"))
      (node (ref "NMOS2") (pin "2") (pinfunction "D_2") (pintype "passive"))
    )
    (net (code "8") (name "Net-(GREEN2-PadA)") (class "Default")
      (node (ref "GREEN2") (pin "A") (pinfunction "A_A") (pintype "passive"))
      (node (ref "R9") (pin "2") (pinfunction "2_2") (pintype "passive"))
    )
    (net (code "9") (name "Net-(GREEN3-C)") (class "Default")
      (node (ref "GREEN3") (pin "K") (pinfunction "C_K") (pintype "passive"))
      (node (ref "NMOS3") (pin "2") (pinfunction "D_2") (pintype "passive"))
    )
    (net (code "10") (name "Net-(GREEN3-PadA)") (class "Default")
      (node (ref "GREEN3") (pin "A") (pinfunction "A_A") (pintype "passive"))
      (node (ref "R12") (pin "2") (pinfunction "2_2") (pintype "passive"))
    )
    (net (code "11") (name "Net-(GREEN4-C)") (class "Default")
      (node (ref "GREEN4") (pin "K") (pinfunction "C_K") (pintype "passive"))
      (node (ref "NMOS4") (pin "2") (pinfunction "D_2") (pintype "passive"))
    )
    (net (code "12") (name "Net-(GREEN4-PadA)") (class "Default")
      (node (ref "GREEN4") (pin "A") (pinfunction "A_A") (pintype "passive"))
      (node (ref "R15") (pin "2") (pinfunction "2_2") (pintype "passive"))
    )
    (net (code "13") (name "Net-(GREEN5-C)") (class "Default")
      (node (ref "GREEN5") (pin "K") (pinfunction "C_K") (pintype "passive"))
      (node (ref "NMOS5") (pin "2") (pinfunction "D_2") (pintype "passive"))
    )
    (net (code "14") (name "Net-(GREEN5-PadA)") (class "Default")
      (node (ref "GREEN5") (pin "A") (pinfunction "A_A") (pintype "passive"))
      (node (ref "R18") (pin "2") (pinfunction "2_2") (pintype "passive"))
    )
    (net (code "15") (name "Net-(GREEN6-C)") (class "Default")
      (node (ref "GREEN6") (pin "K") (pinfunction "C_K") (pintype "passive"))
      (node (ref "NMOS6") (pin "2") (pinfunction "D_2") (pintype "passive"))
    )
    (net (code "16") (name "Net-(GREEN6-PadA)") (class "Default")
      (node (ref "GREEN6") (pin "A") (pinfunction "A_A") (pintype "passive"))
      (node (ref "R21") (pin "2") (pinfunction "2_2") (pintype "passive"))
    )
    (net (code "17") (name "Net-(GREEN7-C)") (class "Default")
      (node (ref "GREEN7") (pin "K") (pinfunction "C_K") (pintype "passive"))
      (node (ref "NMOS7") (pin "2") (pinfunction "D_2") (pintype "passive"))
    )
    (net (code "18") (name "Net-(GREEN7-PadA)") (class "Default")
      (node (ref "GREEN7") (pin "A") (pinfunction "A_A") (pintype "passive"))
      (node (ref "R24") (pin "2") (pinfunction "2_2") (pintype "passive"))
    )
    (net (code "19") (name "Net-(GREEN8-C)") (class "Default")
      (node (ref "GREEN8") (pin "K") (pinfunction "C_K") (pintype "passive"))
      (node (ref "NMOS8") (pin "2") (pinfunction "D_2") (pintype "passive"))
    )
    (net (code "20") (name "Net-(GREEN8-PadA)") (class "Default")
      (node (ref "GREEN8") (pin "A") (pinfunction "A_A") (pintype "passive"))
      (node (ref "R27") (pin "2") (pinfunction "2_2") (pintype "passive"))
    )
    (net (code "21") (name "Net-(PMOS-S)") (class "Default")
      (node (ref "PMOS") (pin "1") (pinfunction "S_1") (pintype "passive"))
      (node (ref "R4") (pin "1") (pinfunction "1_1") (pintype "passive"))
    )
    (net (code "22") (name "Net-(PMOS1-S)") (class "Default")
      (node (ref "PMOS1") (pin "1") (pinfunction "S_1") (pintype "passive"))
      (node (ref "R1") (pin "1") (pinfunction "1_1") (pintype "passive"))
    )
    (net (code "23") (name "Net-(PMOS2-S)") (class "Default")
      (node (ref "PMOS2") (pin "1") (pinfunction "S_1") (pintype "passive"))
      (node (ref "R7") (pin "1") (pinfunction "1_1") (pintype "passive"))
    )
    (net (code "24") (name "Net-(PMOS3-S)") (class "Default")
      (node (ref "PMOS3") (pin "1") (pinfunction "S_1") (pintype "passive"))
      (node (ref "R10") (pin "1") (pinfunction "1_1") (pintype "passive"))
    )
    (net (code "25") (name "Net-(PMOS4-S)") (class "Default")
      (node (ref "PMOS4") (pin "1") (pinfunction "S_1") (pintype "passive"))
      (node (ref "R13") (pin "1") (pinfunction "1_1") (pintype "passive"))
    )
    (net (code "26") (name "Net-(PMOS5-S)") (class "Default")
      (node (ref "PMOS5") (pin "1") (pinfunction "S_1") (pintype "passive"))
      (node (ref "R16") (pin "1") (pinfunction "1_1") (pintype "passive"))
    )
    (net (code "27") (name "Net-(PMOS6-S)") (class "Default")
      (node (ref "PMOS6") (pin "1") (pinfunction "S_1") (pintype "passive"))
      (node (ref "R19") (pin "1") (pinfunction "1_1") (pintype "passive"))
    )
    (net (code "28") (name "Net-(PMOS7-S)") (class "Default")
      (node (ref "PMOS7") (pin "1") (pinfunction "S_1") (pintype "passive"))
      (node (ref "R22") (pin "1") (pinfunction "1_1") (pintype "passive"))
    )
    (net (code "29") (name "Net-(PMOS8-S)") (class "Default")
      (node (ref "PMOS8") (pin "1") (pinfunction "S_1") (pintype "passive"))
      (node (ref "R25") (pin "1") (pinfunction "1_1") (pintype "passive"))
    )
    (net (code "30") (name "Net-(PS1-VIN)") (class "Default")
      (node (ref "C2") (pin "1") (pinfunction "1_1") (pintype "passive"))
      (node (ref "L1") (pin "2") (pinfunction "2_2") (pintype "passive"))
      (node (ref "PS1") (pin "2") (pinfunction "VIN_2") (pintype "input"))
    )
    (net (code "31") (name "Net-(PS2-VIN)") (class "Default")
      (node (ref "C5") (pin "1") (pinfunction "1_1") (pintype "passive"))
      (node (ref "L2") (pin "2") (pinfunction "2_2") (pintype "passive"))
      (node (ref "PS2") (pin "2") (pinfunction "VIN_2") (pintype "input"))
    )
    (net (code "32") (name "Net-(PS3-VIN)") (class "Default")
      (node (ref "C8") (pin "1") (pinfunction "1_1") (pintype "passive"))
      (node (ref "L3") (pin "2") (pinfunction "2_2") (pintype "passive"))
      (node (ref "PS3") (pin "2") (pinfunction "VIN_2") (pintype "input"))
    )
    (net (code "33") (name "Net-(PS4-VIN)") (class "Default")
      (node (ref "C11") (pin "1") (pinfunction "1_1") (pintype "passive"))
      (node (ref "L4") (pin "2") (pinfunction "2_2") (pintype "passive"))
      (node (ref "PS4") (pin "2") (pinfunction "VIN_2") (pintype "input"))
    )
    (net (code "34") (name "Net-(PS5-VIN)") (class "Default")
      (node (ref "C14") (pin "1") (pinfunction "1_1") (pintype "passive"))
      (node (ref "L5") (pin "2") (pinfunction "2_2") (pintype "passive"))
      (node (ref "PS5") (pin "2") (pinfunction "VIN_2") (pintype "input"))
    )
    (net (code "35") (name "Net-(PS6-VIN)") (class "Default")
      (node (ref "C17") (pin "1") (pinfunction "1_1") (pintype "passive"))
      (node (ref "L6") (pin "2") (pinfunction "2_2") (pintype "passive"))
      (node (ref "PS6") (pin "2") (pinfunction "VIN_2") (pintype "input"))
    )
    (net (code "36") (name "Net-(PS7-VIN)") (class "Default")
      (node (ref "C20") (pin "1") (pinfunction "1_1") (pintype "passive"))
      (node (ref "L7") (pin "2") (pinfunction "2_2") (pintype "passive"))
      (node (ref "PS7") (pin "2") (pinfunction "VIN_2") (pintype "input"))
    )
    (net (code "37") (name "Net-(PS8-VIN)") (class "Default")
      (node (ref "C23") (pin "1") (pinfunction "1_1") (pintype "passive"))
      (node (ref "L8") (pin "2") (pinfunction "2_2") (pintype "passive"))
      (node (ref "PS8") (pin "2") (pinfunction "VIN_2") (pintype "input"))
    )
    (net (code "38") (name "Net-(PS9-VIN)") (class "Default")
      (node (ref "C26") (pin "1") (pinfunction "1_1") (pintype "passive"))
      (node (ref "L9") (pin "2") (pinfunction "2_2") (pintype "passive"))
      (node (ref "PS9") (pin "2") (pinfunction "VIN_2") (pintype "input"))
    )
    (net (code "39") (name "Net-(R1-Pad2)") (class "Default")
      (node (ref "R1") (pin "2") (pinfunction "2_2") (pintype "passive"))
      (node (ref "RED1") (pin "A") (pinfunction "A_A") (pintype "passive"))
    )
    (net (code "40") (name "Net-(R4-Pad2)") (class "Default")
      (node (ref "R4") (pin "2") (pinfunction "2_2") (pintype "passive"))
      (node (ref "RED") (pin "A") (pinfunction "A_A") (pintype "passive"))
    )
    (net (code "41") (name "Net-(R7-Pad2)") (class "Default")
      (node (ref "R7") (pin "2") (pinfunction "2_2") (pintype "passive"))
      (node (ref "RED2") (pin "A") (pinfunction "A_A") (pintype "passive"))
    )
    (net (code "42") (name "Net-(R10-Pad2)") (class "Default")
      (node (ref "R10") (pin "2") (pinfunction "2_2") (pintype "passive"))
      (node (ref "RED3") (pin "A") (pinfunction "A_A") (pintype "passive"))
    )
    (net (code "43") (name "Net-(R13-Pad2)") (class "Default")
      (node (ref "R13") (pin "2") (pinfunction "2_2") (pintype "passive"))
      (node (ref "RED4") (pin "A") (pinfunction "A_A") (pintype "passive"))
    )
    (net (code "44") (name "Net-(R16-Pad2)") (class "Default")
      (node (ref "R16") (pin "2") (pinfunction "2_2") (pintype "passive"))
      (node (ref "RED5") (pin "A") (pinfunction "A_A") (pintype "passive"))
    )
    (net (code "45") (name "Net-(R19-Pad2)") (class "Default")
      (node (ref "R19") (pin "2") (pinfunction "2_2") (pintype "passive"))
      (node (ref "RED6") (pin "A") (pinfunction "A_A") (pintype "passive"))
    )
    (net (code "46") (name "Net-(R22-Pad2)") (class "Default")
      (node (ref "R22") (pin "2") (pinfunction "2_2") (pintype "passive"))
      (node (ref "RED7") (pin "A") (pinfunction "A_A") (pintype "passive"))
    )
    (net (code "47") (name "Net-(R25-Pad2)") (class "Default")
      (node (ref "R25") (pin "2") (pinfunction "2_2") (pintype "passive"))
      (node (ref "RED8") (pin "A") (pinfunction "A_A") (pintype "passive"))
    )
    (net (code "48") (name "SWITCH1") (class "Default")
      (node (ref "C3") (pin "1") (pinfunction "1_1") (pintype "passive"))
      (node (ref "JP2") (pin "1") (pinfunction "1_1") (pintype "passive"))
      (node (ref "PMOS") (pin "3") (pinfunction "D_3") (pintype "passive"))
      (node (ref "PS1") (pin "4") (pinfunction "+VOUT_4") (pintype "output"))
      (node (ref "R3") (pin "1") (pinfunction "1_1") (pintype "passive"))
    )
    (net (code "49") (name "SWITCH2") (class "Default")
      (node (ref "C6") (pin "1") (pinfunction "1_1") (pintype "passive"))
      (node (ref "JP3") (pin "1") (pinfunction "1_1") (pintype "passive"))
      (node (ref "PMOS1") (pin "3") (pinfunction "D_3") (pintype "passive"))
      (node (ref "PS2") (pin "4") (pinfunction "+VOUT_4") (pintype "output"))
      (node (ref "R6") (pin "1") (pinfunction "1_1") (pintype "passive"))
    )
    (net (code "50") (name "SWITCH3") (class "Default")
      (node (ref "C9") (pin "1") (pinfunction "1_1") (pintype "passive"))
      (node (ref "JP4") (pin "1") (pinfunction "1_1") (pintype "passive"))
      (node (ref "PMOS2") (pin "3") (pinfunction "D_3") (pintype "passive"))
      (node (ref "PS3") (pin "4") (pinfunction "+VOUT_4") (pintype "output"))
      (node (ref "R9") (pin "1") (pinfunction "1_1") (pintype "passive"))
    )
    (net (code "51") (name "SWITCH4") (class "Default")
      (node (ref "C18") (pin "1") (pinfunction "1_1") (pintype "passive"))
      (node (ref "JP5") (pin "1") (pinfunction "1_1") (pintype "passive"))
      (node (ref "PMOS5") (pin "3") (pinfunction "D_3") (pintype "passive"))
      (node (ref "PS6") (pin "4") (pinfunction "+VOUT_4") (pintype "output"))
      (node (ref "R18") (pin "1") (pinfunction "1_1") (pintype "passive"))
    )
    (net (code "52") (name "SWITCH5") (class "Default")
      (node (ref "C15") (pin "1") (pinfunction "1_1") (pintype "passive"))
      (node (ref "JP6") (pin "1") (pinfunction "1_1") (pintype "passive"))
      (node (ref "PMOS4") (pin "3") (pinfunction "D_3") (pintype "passive"))
      (node (ref "PS5") (pin "4") (pinfunction "+VOUT_4") (pintype "output"))
      (node (ref "R15") (pin "1") (pinfunction "1_1") (pintype "passive"))
    )
    (net (code "53") (name "SWITCH6") (class "Default")
      (node (ref "C12") (pin "1") (pinfunction "1_1") (pintype "passive"))
      (node (ref "JP7") (pin "1") (pinfunction "1_1") (pintype "passive"))
      (node (ref "PMOS3") (pin "3") (pinfunction "D_3") (pintype "passive"))
      (node (ref "PS4") (pin "4") (pinfunction "+VOUT_4") (pintype "output"))
      (node (ref "R12") (pin "1") (pinfunction "1_1") (pintype "passive"))
    )
    (net (code "54") (name "SWITCH7") (class "Default")
      (node (ref "C27") (pin "1") (pinfunction "1_1") (pintype "passive"))
      (node (ref "JP8") (pin "1") (pinfunction "1_1") (pintype "passive"))
      (node (ref "PMOS8") (pin "3") (pinfunction "D_3") (pintype "passive"))
      (node (ref "PS9") (pin "4") (pinfunction "+VOUT_4") (pintype "output"))
      (node (ref "R27") (pin "1") (pinfunction "1_1") (pintype "passive"))
    )
    (net (code "55") (name "SWITCH8") (class "Default")
      (node (ref "C24") (pin "1") (pinfunction "1_1") (pintype "passive"))
      (node (ref "JP9") (pin "1") (pinfunction "1_1") (pintype "passive"))
      (node (ref "PMOS7") (pin "3") (pinfunction "D_3") (pintype "passive"))
      (node (ref "PS8") (pin "4") (pinfunction "+VOUT_4") (pintype "output"))
      (node (ref "R24") (pin "1") (pinfunction "1_1") (pintype "passive"))
    )
    (net (code "56") (name "SWITCH9") (class "Default")
      (node (ref "C21") (pin "1") (pinfunction "1_1") (pintype "passive"))
      (node (ref "JP10") (pin "1") (pinfunction "1_1") (pintype "passive"))
      (node (ref "PMOS6") (pin "3") (pinfunction "D_3") (pintype "passive"))
      (node (ref "PS7") (pin "4") (pinfunction "+VOUT_4") (pintype "output"))
      (node (ref "R21") (pin "1") (pinfunction "1_1") (pintype "passive"))
    )
    (net (code "57") (name "SW_SIG1") (class "Default")
      (node (ref "JP11") (pin "5") (pinfunction "5_5") (pintype "passive"))
      (node (ref "JP2") (pin "2") (pinfunction "2_2") (pintype "passive"))
      (node (ref "NMOS") (pin "1") (pinfunction "G_1") (pintype "passive"))
      (node (ref "PMOS") (pin "2") (pinfunction "G_2") (pintype "passive"))
      (node (ref "R5") (pin "1") (pinfunction "1_1") (pintype "passive"))
    )
    (net (code "58") (name "SW_SIG2") (class "Default")
      (node (ref "JP11") (pin "4") (pinfunction "4_4") (pintype "passive"))
      (node (ref "JP3") (pin "2") (pinfunction "2_2") (pintype "passive"))
      (node (ref "NMOS1") (pin "1") (pinfunction "G_1") (pintype "passive"))
      (node (ref "PMOS1") (pin "2") (pinfunction "G_2") (pintype "passive"))
      (node (ref "R2") (pin "1") (pinfunction "1_1") (pintype "passive"))
    )
    (net (code "59") (name "SW_SIG3") (class "Default")
      (node (ref "JP11") (pin "12") (pinfunction "12_12") (pintype "passive"))
      (node (ref "JP4") (pin "2") (pinfunction "2_2") (pintype "passive"))
      (node (ref "NMOS2") (pin "1") (pinfunction "G_1") (pintype "passive"))
      (node (ref "PMOS2") (pin "2") (pinfunction "G_2") (pintype "passive"))
      (node (ref "R8") (pin "1") (pinfunction "1_1") (pintype "passive"))
    )
    (net (code "60") (name "SW_SIG4") (class "Default")
      (node (ref "JP11") (pin "10") (pinfunction "10_10") (pintype "passive"))
      (node (ref "JP5") (pin "2") (pinfunction "2_2") (pintype "passive"))
      (node (ref "NMOS5") (pin "1") (pinfunction "G_1") (pintype "passive"))
      (node (ref "PMOS5") (pin "2") (pinfunction "G_2") (pintype "passive"))
      (node (ref "R17") (pin "1") (pinfunction "1_1") (pintype "passive"))
    )
    (net (code "61") (name "SW_SIG5") (class "Default")
      (node (ref "JP11") (pin "8") (pinfunction "8_8") (pintype "passive"))
      (node (ref "JP6") (pin "2") (pinfunction "2_2") (pintype "passive"))
      (node (ref "NMOS4") (pin "1") (pinfunction "G_1") (pintype "passive"))
      (node (ref "PMOS4") (pin "2") (pinfunction "G_2") (pintype "passive"))
      (node (ref "R14") (pin "1") (pinfunction "1_1") (pintype "passive"))
    )
    (net (code "62") (name "SW_SIG6") (class "Default")
      (node (ref "JP11") (pin "6") (pinfunction "6_6") (pintype "passive"))
      (node (ref "JP7") (pin "2") (pinfunction "2_2") (pintype "passive"))
      (node (ref "NMOS3") (pin "1") (pinfunction "G_1") (pintype "passive"))
      (node (ref "PMOS3") (pin "2") (pinfunction "G_2") (pintype "passive"))
      (node (ref "R11") (pin "1") (pinfunction "1_1") (pintype "passive"))
    )
    (net (code "63") (name "SW_SIG7") (class "Default")
      (node (ref "JP11") (pin "11") (pinfunction "11_11") (pintype "passive"))
      (node (ref "JP8") (pin "2") (pinfunction "2_2") (pintype "passive"))
      (node (ref "NMOS8") (pin "1") (pinfunction "G_1") (pintype "passive"))
      (node (ref "PMOS8") (pin "2") (pinfunction "G_2") (pintype "passive"))
      (node (ref "R26") (pin "1") (pinfunction "1_1") (pintype "passive"))
    )
    (net (code "64") (name "SW_SIG8") (class "Default")
      (node (ref "JP11") (pin "9") (pinfunction "9_9") (pintype "passive"))
      (node (ref "JP9") (pin "2") (pinfunction "2_2") (pintype "passive"))
      (node (ref "NMOS7") (pin "1") (pinfunction "G_1") (pintype "passive"))
      (node (ref "PMOS7") (pin "2") (pinfunction "G_2") (pintype "passive"))
      (node (ref "R23") (pin "1") (pinfunction "1_1") (pintype "passive"))
    )
    (net (code "65") (name "SW_SIG9") (class "Default")
      (node (ref "JP10") (pin "2") (pinfunction "2_2") (pintype "passive"))
      (node (ref "JP11") (pin "7") (pinfunction "7_7") (pintype "passive"))
      (node (ref "NMOS6") (pin "1") (pinfunction "G_1") (pintype "passive"))
      (node (ref "PMOS6") (pin "2") (pinfunction "G_2") (pintype "passive"))
      (node (ref "R20") (pin "1") (pinfunction "1_1") (pintype "passive"))
    )
  )
)
